# micro_led.net
KiCad netlist of a schematic drawn in EAGLE
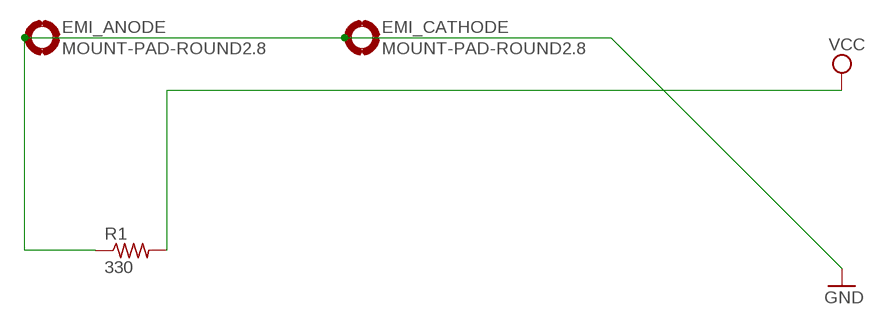
[diagram p0: schematic, sheet 1]

(export (version "E")
  (design (tool "Eeschema 10.0.6"))
  (components
    (comp (ref "EMI_ANODE")
      (value "MOUNT-PAD-ROUND2.8")
      (footprint "eagle-import:2,8-PAD")
      (libsource (lib "eagle-import") (part "MOUNT-PAD-ROUND2.8"))
    )
    (comp (ref "EMI_CATHODE")
      (value "MOUNT-PAD-ROUND2.8")
      (footprint "eagle-import:2,8-PAD")
      (libsource (lib "eagle-import") (part "MOUNT-PAD-ROUND2.8"))
    )
    (comp (ref "R1")
      (value "330")
      (footprint "eagle-import:0204V")
      (libsource (lib "eagle-import") (part "R-US_0204/2V"))
    )
  )
  (nets
    (net (code "1") (name "GND") (class "Default")
      (node (ref "EMI_ANODE") (pin "B2,8") (pinfunction "MOUNT_B2,8") (pintype "passive"))
      (node (ref "EMI_CATHODE") (pin "B2,8") (pinfunction "MOUNT_B2,8") (pintype "passive"))
      (node (ref "R1") (pin "1") (pinfunction "1_1") (pintype "passive"))
    )
    (net (code "2") (name "VCC") (class "Default")
      (node (ref "R1") (pin "2") (pinfunction "2_2") (pintype "passive"))
    )
  )
)
